# motorpad.net
KiCad netlist of a schematic drawn in EAGLE
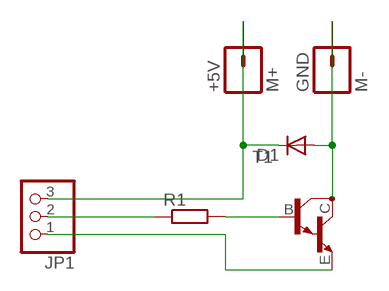
[diagram p0: schematic, sheet 1]

(export (version "E")
  (design (tool "Eeschema 10.0.6"))
  (components
    (comp (ref "+5V")
      (value "M+")
      (footprint "eagle-import:1X01_OFFSET")
      (libsource (lib "eagle-import") (part "M01OFFSET"))
    )
    (comp (ref "D1")
      (value "DIODESOD")
      (footprint "eagle-import:SOD-323")
      (libsource (lib "eagle-import") (part "DIODESOD"))
    )
    (comp (ref "GND")
      (value "M-")
      (footprint "eagle-import:1X01_OFFSET")
      (libsource (lib "eagle-import") (part "M01OFFSET"))
    )
    (comp (ref "JP1")
      (value "PINHD-1X3/90")
      (footprint "eagle-import:1X03_90")
      (libsource (lib "eagle-import") (part "PINHD-1X3/90"))
    )
    (comp (ref "R1")
      (value "R-EU_R0603")
      (footprint "eagle-import:R0603")
      (libsource (lib "eagle-import") (part "R-EU_R0603"))
    )
    (comp (ref "T1")
      (value "MMBTA13LT1-NPN_DARL-SOT23-BEC")
      (footprint "eagle-import:SOT23-BEC")
      (libsource (lib "eagle-import") (part "-NPN_DARL-SOT23-BECMMBTA13LT1"))
    )
  )
  (nets
    (net (code "1") (name "Net-(D1-A)") (class "Default")
      (node (ref "D1") (pin "2") (pinfunction "A_2") (pintype "passive"))
      (node (ref "GND") (pin "1") (pinfunction "1_1") (pintype "passive"))
      (node (ref "T1") (pin "C") (pinfunction "C_C") (pintype "passive"))
    )
    (net (code "2") (name "Net-(D1-C)") (class "Default")
      (node (ref "+5V") (pin "1") (pinfunction "1_1") (pintype "passive"))
      (node (ref "D1") (pin "1") (pinfunction "C_1") (pintype "passive"))
      (node (ref "JP1") (pin "3") (pinfunction "3_3") (pintype "passive"))
    )
    (net (code "3") (name "Net-(JP1-Pad1)") (class "Default")
      (node (ref "JP1") (pin "1") (pinfunction "1_1") (pintype "passive"))
      (node (ref "T1") (pin "E") (pinfunction "E_E") (pintype "passive"))
    )
    (net (code "4") (name "Net-(JP1-Pad2)") (class "Default")
      (node (ref "JP1") (pin "2") (pinfunction "2_2") (pintype "passive"))
      (node (ref "R1") (pin "1") (pinfunction "1_1") (pintype "passive"))
    )
    (net (code "5") (name "Net-(R1-Pad2)") (class "Default")
      (node (ref "R1") (pin "2") (pinfunction "2_2") (pintype "passive"))
      (node (ref "T1") (pin "B") (pinfunction "B_B") (pintype "passive"))
    )
  )
)
